# v2.net
KiCad netlist of a schematic drawn in EAGLE
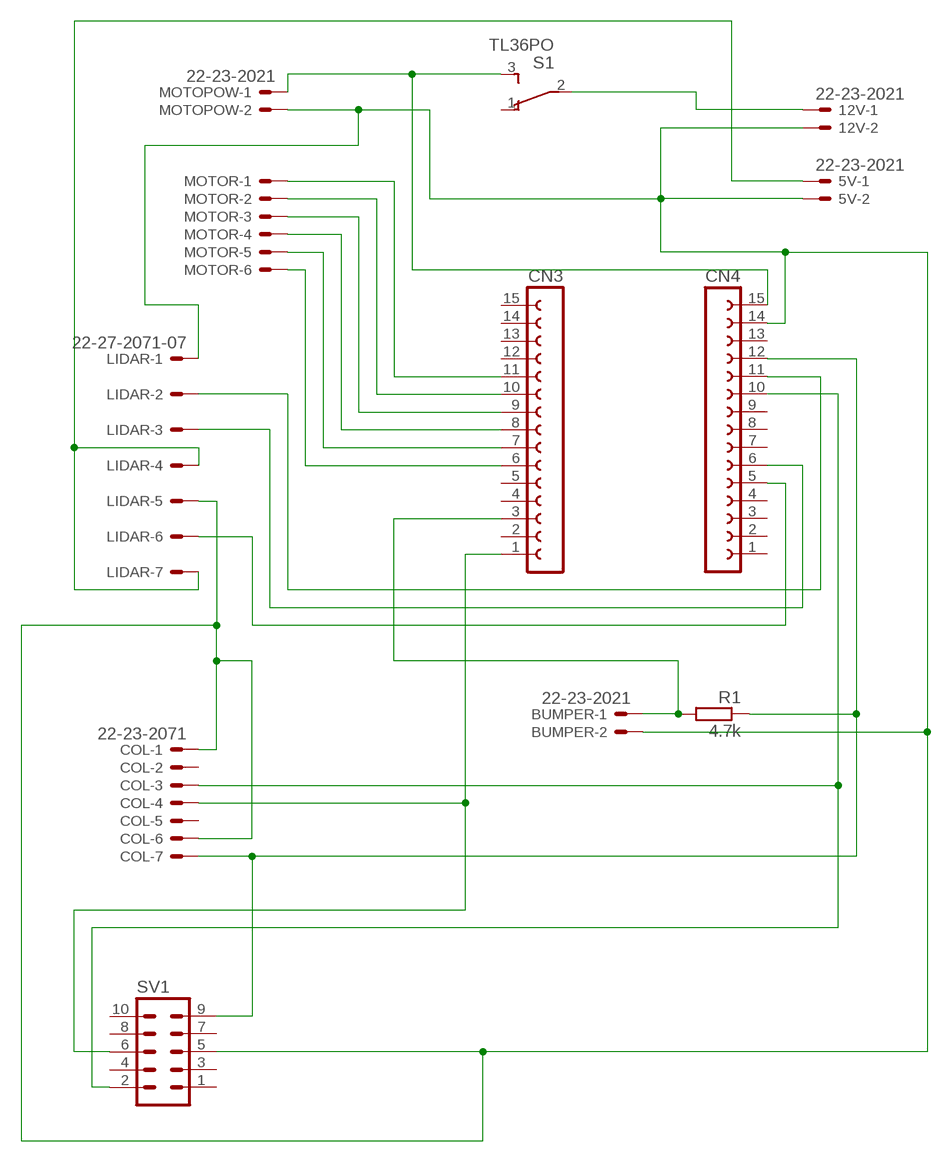
[diagram p0: schematic, sheet 1]

(export (version "E")
  (design (tool "Eeschema 10.0.6"))
  (components
    (comp (ref "5V")
      (value "22-23-2021")
      (footprint "eagle-import:22-23-2021")
      (fields (field (name "MF") "MOLEX"))
      (libsource (lib "eagle-import") (part "22-23-2021"))
    )
    (comp (ref "12V")
      (value "22-23-2021")
      (footprint "eagle-import:22-23-2021")
      (fields (field (name "MF") "MOLEX"))
      (libsource (lib "eagle-import") (part "22-23-2021"))
    )
    (comp (ref "BUMPER")
      (value "22-23-2021")
      (footprint "eagle-import:22-23-2021")
      (fields (field (name "MF") "MOLEX"))
      (libsource (lib "eagle-import") (part "22-23-2021"))
    )
    (comp (ref "CN3")
      (value "FE15-1")
      (footprint "eagle-import:FE15")
      (libsource (lib "eagle-import") (part "FE15-1"))
    )
    (comp (ref "CN4")
      (value "FE15-1")
      (footprint "eagle-import:FE15")
      (libsource (lib "eagle-import") (part "FE15-1"))
    )
    (comp (ref "COL")
      (value "22-23-2071")
      (footprint "eagle-import:22-23-2071")
      (fields (field (name "MF") "MOLEX"))
      (libsource (lib "eagle-import") (part "22-23-2071"))
    )
    (comp (ref "LIDAR")
      (value "22-27-2071-07")
      (footprint "eagle-import:6410-07")
      (fields (field (name "MF") "MOLEX"))
      (libsource (lib "eagle-import") (part "22-?-0727-2071"))
    )
    (comp (ref "MOTOPOW")
      (value "22-23-2021")
      (footprint "eagle-import:22-23-2021")
      (fields (field (name "MF") "MOLEX"))
      (libsource (lib "eagle-import") (part "22-23-2021"))
    )
    (comp (ref "MOTOR")
      (value "22-23-2061")
      (footprint "eagle-import:22-23-2061")
      (fields (field (name "MF") "MOLEX"))
      (libsource (lib "eagle-import") (part "22-23-2061"))
    )
    (comp (ref "R1")
      (value "4.7k")
      (footprint "eagle-import:R1206")
      (libsource (lib "eagle-import") (part "R-EU_R1206"))
    )
    (comp (ref "S1")
      (value "TL36PO")
      (footprint "eagle-import:TL3XPO")
      (libsource (lib "eagle-import") (part "TL36PO"))
    )
    (comp (ref "SV1")
      (value "MA05-2")
      (footprint "eagle-import:MA05-2")
      (libsource (lib "eagle-import") (part "MA05-2"))
    )
  )
  (nets
    (net (code "1") (name "Net-(5VA-S)") (class "Default")
      (node (ref "5V") (pin "1") (pinfunction "S_1") (pintype "passive"))
      (node (ref "LIDAR") (pin "4") (pinfunction "S_4") (pintype "passive"))
      (node (ref "LIDAR") (pin "7") (pinfunction "S_7") (pintype "passive"))
    )
    (net (code "2") (name "Net-(12VA-S)") (class "Default")
      (node (ref "12V") (pin "1") (pinfunction "S_1") (pintype "passive"))
      (node (ref "S1") (pin "2") (pinfunction "P_2") (pintype "passive"))
    )
    (net (code "3") (name "Net-(12VB-S)") (class "Default")
      (node (ref "12V") (pin "2") (pinfunction "S_2") (pintype "passive"))
      (node (ref "5V") (pin "2") (pinfunction "S_2") (pintype "passive"))
      (node (ref "BUMPER") (pin "2") (pinfunction "S_2") (pintype "passive"))
      (node (ref "CN4") (pin "14") (pinfunction "14_14") (pintype "passive"))
      (node (ref "COL") (pin "1") (pinfunction "S_1") (pintype "passive"))
      (node (ref "COL") (pin "6") (pinfunction "S_6") (pintype "passive"))
      (node (ref "LIDAR") (pin "1") (pinfunction "S_1") (pintype "passive"))
      (node (ref "LIDAR") (pin "5") (pinfunction "S_5") (pintype "passive"))
      (node (ref "MOTOPOW") (pin "2") (pinfunction "S_2") (pintype "passive"))
      (node (ref "SV1") (pin "5") (pinfunction "5_5") (pintype "passive"))
    )
    (net (code "4") (name "Net-(BUMPERA-S)") (class "Default")
      (node (ref "BUMPER") (pin "1") (pinfunction "S_1") (pintype "passive"))
      (node (ref "CN3") (pin "3") (pinfunction "3_3") (pintype "passive"))
      (node (ref "R1") (pin "2") (pinfunction "2_2") (pintype "passive"))
    )
    (net (code "5") (name "Net-(COLC-S)") (class "Default")
      (node (ref "CN4") (pin "10") (pinfunction "10_10") (pintype "passive"))
      (node (ref "COL") (pin "3") (pinfunction "S_3") (pintype "passive"))
      (node (ref "SV1") (pin "2") (pinfunction "2_2") (pintype "passive"))
    )
    (net (code "6") (name "Net-(COLD-S)") (class "Default")
      (node (ref "CN3") (pin "1") (pinfunction "1_1") (pintype "passive"))
      (node (ref "COL") (pin "4") (pinfunction "S_4") (pintype "passive"))
      (node (ref "SV1") (pin "6") (pinfunction "6_6") (pintype "passive"))
    )
    (net (code "7") (name "Net-(COLG-S)") (class "Default")
      (node (ref "CN4") (pin "12") (pinfunction "12_12") (pintype "passive"))
      (node (ref "COL") (pin "7") (pinfunction "S_7") (pintype "passive"))
      (node (ref "R1") (pin "1") (pinfunction "1_1") (pintype "passive"))
      (node (ref "SV1") (pin "9") (pinfunction "9_9") (pintype "passive"))
    )
    (net (code "8") (name "Net-(LIDARB-S)") (class "Default")
      (node (ref "CN4") (pin "11") (pinfunction "11_11") (pintype "passive"))
      (node (ref "LIDAR") (pin "2") (pinfunction "S_2") (pintype "passive"))
    )
    (net (code "9") (name "Net-(LIDARC-S)") (class "Default")
      (node (ref "CN4") (pin "6") (pinfunction "6_6") (pintype "passive"))
      (node (ref "LIDAR") (pin "3") (pinfunction "S_3") (pintype "passive"))
    )
    (net (code "10") (name "Net-(LIDARF-S)") (class "Default")
      (node (ref "CN4") (pin "5") (pinfunction "5_5") (pintype "passive"))
      (node (ref "LIDAR") (pin "6") (pinfunction "S_6") (pintype "passive"))
    )
    (net (code "11") (name "Net-(MOTOPOWA-S)") (class "Default")
      (node (ref "CN4") (pin "15") (pinfunction "15_15") (pintype "passive"))
      (node (ref "MOTOPOW") (pin "1") (pinfunction "S_1") (pintype "passive"))
      (node (ref "S1") (pin "3") (pinfunction "S_3") (pintype "passive"))
    )
    (net (code "12") (name "Net-(MOTORA-S)") (class "Default")
      (node (ref "CN3") (pin "11") (pinfunction "11_11") (pintype "passive"))
      (node (ref "MOTOR") (pin "1") (pinfunction "S_1") (pintype "passive"))
    )
    (net (code "13") (name "Net-(MOTORB-S)") (class "Default")
      (node (ref "CN3") (pin "10") (pinfunction "10_10") (pintype "passive"))
      (node (ref "MOTOR") (pin "2") (pinfunction "S_2") (pintype "passive"))
    )
    (net (code "14") (name "Net-(MOTORC-S)") (class "Default")
      (node (ref "CN3") (pin "9") (pinfunction "9_9") (pintype "passive"))
      (node (ref "MOTOR") (pin "3") (pinfunction "S_3") (pintype "passive"))
    )
    (net (code "15") (name "Net-(MOTORD-S)") (class "Default")
      (node (ref "CN3") (pin "8") (pinfunction "8_8") (pintype "passive"))
      (node (ref "MOTOR") (pin "4") (pinfunction "S_4") (pintype "passive"))
    )
    (net (code "16") (name "Net-(MOTORE-S)") (class "Default")
      (node (ref "CN3") (pin "7") (pinfunction "7_7") (pintype "passive"))
      (node (ref "MOTOR") (pin "5") (pinfunction "S_5") (pintype "passive"))
    )
    (net (code "17") (name "Net-(MOTORF-S)") (class "Default")
      (node (ref "CN3") (pin "6") (pinfunction "6_6") (pintype "passive"))
      (node (ref "MOTOR") (pin "6") (pinfunction "S_6") (pintype "passive"))
    )
    (net (code "18") (name "unconnected-(CN3-Pad2)") (class "Default")
      (node (ref "CN3") (pin "2") (pinfunction "2_2") (pintype "passive"))
    )
    (net (code "19") (name "unconnected-(CN3-Pad4)") (class "Default")
      (node (ref "CN3") (pin "4") (pinfunction "4_4") (pintype "passive"))
    )
    (net (code "20") (name "unconnected-(CN3-Pad5)") (class "Default")
      (node (ref "CN3") (pin "5") (pinfunction "5_5") (pintype "passive"))
    )
    (net (code "21") (name "unconnected-(CN3-Pad12)") (class "Default")
      (node (ref "CN3") (pin "12") (pinfunction "12_12") (pintype "passive"))
    )
    (net (code "22") (name "unconnected-(CN3-Pad13)") (class "Default")
      (node (ref "CN3") (pin "13") (pinfunction "13_13") (pintype "passive"))
    )
    (net (code "23") (name "unconnected-(CN3-Pad14)") (class "Default")
      (node (ref "CN3") (pin "14") (pinfunction "14_14") (pintype "passive"))
    )
    (net (code "24") (name "unconnected-(CN3-Pad15)") (class "Default")
      (node (ref "CN3") (pin "15") (pinfunction "15_15") (pintype "passive"))
    )
    (net (code "25") (name "unconnected-(CN4-Pad1)") (class "Default")
      (node (ref "CN4") (pin "1") (pinfunction "1_1") (pintype "passive"))
    )
    (net (code "26") (name "unconnected-(CN4-Pad2)") (class "Default")
      (node (ref "CN4") (pin "2") (pinfunction "2_2") (pintype "passive"))
    )
    (net (code "27") (name "unconnected-(CN4-Pad3)") (class "Default")
      (node (ref "CN4") (pin "3") (pinfunction "3_3") (pintype "passive"))
    )
    (net (code "28") (name "unconnected-(CN4-Pad4)") (class "Default")
      (node (ref "CN4") (pin "4") (pinfunction "4_4") (pintype "passive"))
    )
    (net (code "29") (name "unconnected-(CN4-Pad7)") (class "Default")
      (node (ref "CN4") (pin "7") (pinfunction "7_7") (pintype "passive"))
    )
    (net (code "30") (name "unconnected-(CN4-Pad8)") (class "Default")
      (node (ref "CN4") (pin "8") (pinfunction "8_8") (pintype "passive"))
    )
    (net (code "31") (name "unconnected-(CN4-Pad9)") (class "Default")
      (node (ref "CN4") (pin "9") (pinfunction "9_9") (pintype "passive"))
    )
    (net (code "32") (name "unconnected-(CN4-Pad13)") (class "Default")
      (node (ref "CN4") (pin "13") (pinfunction "13_13") (pintype "passive"))
    )
    (net (code "33") (name "unconnected-(COLB-S-Pad2)") (class "Default")
      (node (ref "COL") (pin "2") (pinfunction "S_2") (pintype "passive"))
    )
    (net (code "34") (name "unconnected-(COLE-S-Pad5)") (class "Default")
      (node (ref "COL") (pin "5") (pinfunction "S_5") (pintype "passive"))
    )
    (net (code "35") (name "unconnected-(S1-O-Pad1)") (class "Default")
      (node (ref "S1") (pin "1") (pinfunction "O_1") (pintype "passive"))
    )
    (net (code "36") (name "unconnected-(SV1-Pad1)") (class "Default")
      (node (ref "SV1") (pin "1") (pinfunction "1_1") (pintype "passive"))
    )
    (net (code "37") (name "unconnected-(SV1-Pad3)") (class "Default")
      (node (ref "SV1") (pin "3") (pinfunction "3_3") (pintype "passive"))
    )
    (net (code "38") (name "unconnected-(SV1-Pad4)") (class "Default")
      (node (ref "SV1") (pin "4") (pinfunction "4_4") (pintype "passive"))
    )
    (net (code "39") (name "unconnected-(SV1-Pad7)") (class "Default")
      (node (ref "SV1") (pin "7") (pinfunction "7_7") (pintype "passive"))
    )
    (net (code "40") (name "unconnected-(SV1-Pad8)") (class "Default")
      (node (ref "SV1") (pin "8") (pinfunction "8_8") (pintype "passive"))
    )
    (net (code "41") (name "unconnected-(SV1-Pad10)") (class "Default")
      (node (ref "SV1") (pin "10") (pinfunction "10_10") (pintype "passive"))
    )
  )
)
